# driver_board_ribbon.net
KiCad netlist of a schematic drawn in EAGLE
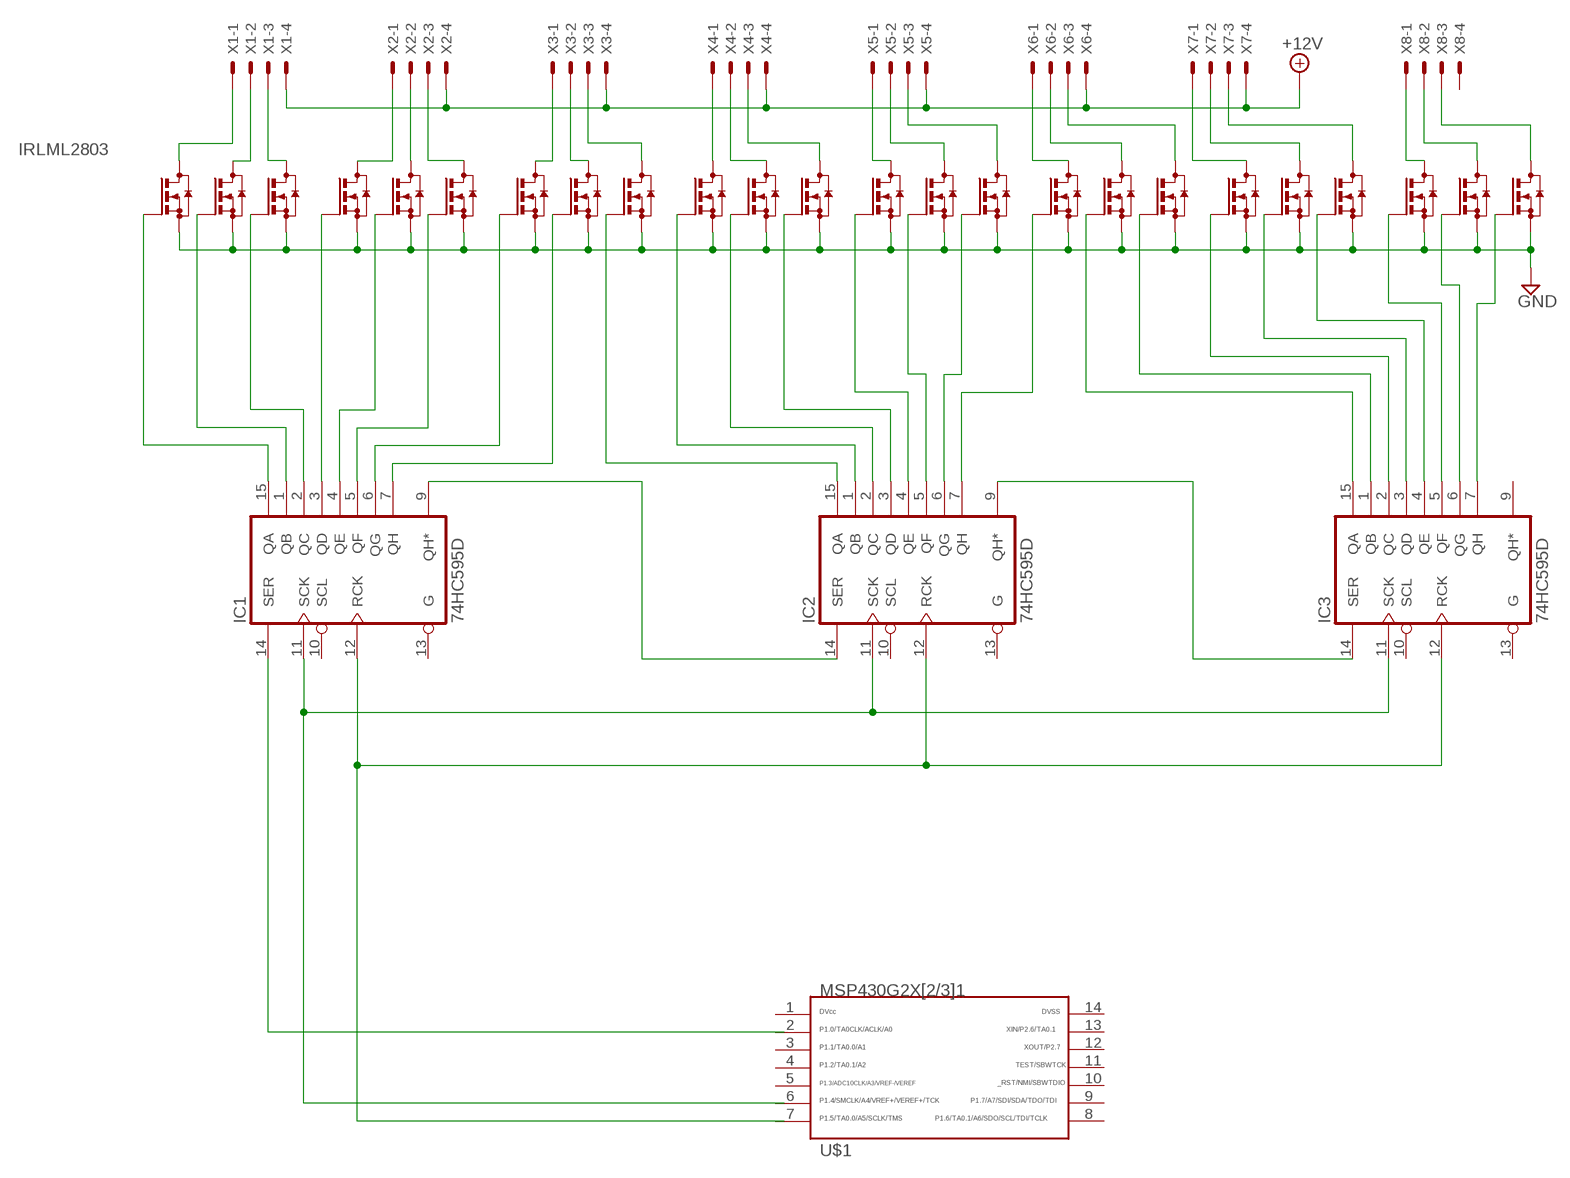
[diagram p0: schematic, sheet 1]

(export (version "E")
  (design (tool "Eeschema 10.0.6"))
  (components
    (comp (ref "IC1")
      (value "74HC595D")
      (footprint "eagle-import:SO16")
      (libsource (lib "eagle-import") (part "74595DHC"))
    )
    (comp (ref "IC2")
      (value "74HC595D")
      (footprint "eagle-import:SO16")
      (libsource (lib "eagle-import") (part "74595DHC"))
    )
    (comp (ref "IC3")
      (value "74HC595D")
      (footprint "eagle-import:SO16")
      (libsource (lib "eagle-import") (part "74595DHC"))
    )
    (comp (ref "U$1")
      (value "G2X[2/3]1---PW14")
      (footprint "eagle-import:PW14")
      (libsource (lib "eagle-import") (part "G2X[2/3]1---PW14"))
    )
    (comp (ref "U$3")
      (value "IRLML2803")
      (footprint "eagle-import:SOT23")
      (libsource (lib "eagle-import") (part "IRLML2803"))
    )
    (comp (ref "U$4")
      (value "IRLML2803")
      (footprint "eagle-import:SOT23")
      (libsource (lib "eagle-import") (part "IRLML2803"))
    )
    (comp (ref "U$5")
      (value "IRLML2803")
      (footprint "eagle-import:SOT23")
      (libsource (lib "eagle-import") (part "IRLML2803"))
    )
    (comp (ref "U$6")
      (value "IRLML2803")
      (footprint "eagle-import:SOT23")
      (libsource (lib "eagle-import") (part "IRLML2803"))
    )
    (comp (ref "U$7")
      (value "IRLML2803")
      (footprint "eagle-import:SOT23")
      (libsource (lib "eagle-import") (part "IRLML2803"))
    )
    (comp (ref "U$8")
      (value "IRLML2803")
      (footprint "eagle-import:SOT23")
      (libsource (lib "eagle-import") (part "IRLML2803"))
    )
    (comp (ref "U$9")
      (value "IRLML2803")
      (footprint "eagle-import:SOT23")
      (libsource (lib "eagle-import") (part "IRLML2803"))
    )
    (comp (ref "U$10")
      (value "IRLML2803")
      (footprint "eagle-import:SOT23")
      (libsource (lib "eagle-import") (part "IRLML2803"))
    )
    (comp (ref "U$11")
      (value "IRLML2803")
      (footprint "eagle-import:SOT23")
      (libsource (lib "eagle-import") (part "IRLML2803"))
    )
    (comp (ref "U$12")
      (value "IRLML2803")
      (footprint "eagle-import:SOT23")
      (libsource (lib "eagle-import") (part "IRLML2803"))
    )
    (comp (ref "U$13")
      (value "IRLML2803")
      (footprint "eagle-import:SOT23")
      (libsource (lib "eagle-import") (part "IRLML2803"))
    )
    (comp (ref "U$14")
      (value "IRLML2803")
      (footprint "eagle-import:SOT23")
      (libsource (lib "eagle-import") (part "IRLML2803"))
    )
    (comp (ref "U$15")
      (value "IRLML2803")
      (footprint "eagle-import:SOT23")
      (libsource (lib "eagle-import") (part "IRLML2803"))
    )
    (comp (ref "U$16")
      (value "IRLML2803")
      (footprint "eagle-import:SOT23")
      (libsource (lib "eagle-import") (part "IRLML2803"))
    )
    (comp (ref "U$17")
      (value "IRLML2803")
      (footprint "eagle-import:SOT23")
      (libsource (lib "eagle-import") (part "IRLML2803"))
    )
    (comp (ref "U$18")
      (value "IRLML2803")
      (footprint "eagle-import:SOT23")
      (libsource (lib "eagle-import") (part "IRLML2803"))
    )
    (comp (ref "U$19")
      (value "IRLML2803")
      (footprint "eagle-import:SOT23")
      (libsource (lib "eagle-import") (part "IRLML2803"))
    )
    (comp (ref "U$20")
      (value "IRLML2803")
      (footprint "eagle-import:SOT23")
      (libsource (lib "eagle-import") (part "IRLML2803"))
    )
    (comp (ref "U$21")
      (value "IRLML2803")
      (footprint "eagle-import:SOT23")
      (libsource (lib "eagle-import") (part "IRLML2803"))
    )
    (comp (ref "U$22")
      (value "IRLML2803")
      (footprint "eagle-import:SOT23")
      (libsource (lib "eagle-import") (part "IRLML2803"))
    )
    (comp (ref "U$23")
      (value "IRLML2803")
      (footprint "eagle-import:SOT23")
      (libsource (lib "eagle-import") (part "IRLML2803"))
    )
    (comp (ref "U$24")
      (value "IRLML2803")
      (footprint "eagle-import:SOT23")
      (libsource (lib "eagle-import") (part "IRLML2803"))
    )
    (comp (ref "U$25")
      (value "IRLML2803")
      (footprint "eagle-import:SOT23")
      (libsource (lib "eagle-import") (part "IRLML2803"))
    )
    (comp (ref "U$26")
      (value "IRLML2803")
      (footprint "eagle-import:SOT23")
      (libsource (lib "eagle-import") (part "IRLML2803"))
    )
    (comp (ref "X1")
      (value "KK-156-4")
      (footprint "eagle-import:KK-156-4")
      (libsource (lib "eagle-import") (part "KK-156-4"))
    )
    (comp (ref "X2")
      (value "KK-156-4")
      (footprint "eagle-import:KK-156-4")
      (libsource (lib "eagle-import") (part "KK-156-4"))
    )
    (comp (ref "X3")
      (value "KK-156-4")
      (footprint "eagle-import:KK-156-4")
      (libsource (lib "eagle-import") (part "KK-156-4"))
    )
    (comp (ref "X4")
      (value "KK-156-4")
      (footprint "eagle-import:KK-156-4")
      (libsource (lib "eagle-import") (part "KK-156-4"))
    )
    (comp (ref "X5")
      (value "KK-156-4")
      (footprint "eagle-import:KK-156-4")
      (libsource (lib "eagle-import") (part "KK-156-4"))
    )
    (comp (ref "X6")
      (value "KK-156-4")
      (footprint "eagle-import:KK-156-4")
      (libsource (lib "eagle-import") (part "KK-156-4"))
    )
    (comp (ref "X7")
      (value "KK-156-4")
      (footprint "eagle-import:KK-156-4")
      (libsource (lib "eagle-import") (part "KK-156-4"))
    )
    (comp (ref "X8")
      (value "KK-156-4")
      (footprint "eagle-import:KK-156-4")
      (libsource (lib "eagle-import") (part "KK-156-4"))
    )
  )
  (nets
    (net (code "1") (name "+12V") (class "Default")
      (node (ref "X1") (pin "4") (pinfunction "S_4") (pintype "passive"))
      (node (ref "X2") (pin "4") (pinfunction "S_4") (pintype "passive"))
      (node (ref "X3") (pin "4") (pinfunction "S_4") (pintype "passive"))
      (node (ref "X4") (pin "4") (pinfunction "S_4") (pintype "passive"))
      (node (ref "X5") (pin "4") (pinfunction "S_4") (pintype "passive"))
      (node (ref "X6") (pin "4") (pinfunction "S_4") (pintype "passive"))
      (node (ref "X7") (pin "4") (pinfunction "S_4") (pintype "passive"))
    )
    (net (code "2") (name "GND") (class "Default")
      (node (ref "U$10") (pin "2") (pinfunction "S_2") (pintype "passive"))
      (node (ref "U$11") (pin "2") (pinfunction "S_2") (pintype "passive"))
      (node (ref "U$12") (pin "2") (pinfunction "S_2") (pintype "passive"))
      (node (ref "U$13") (pin "2") (pinfunction "S_2") (pintype "passive"))
      (node (ref "U$14") (pin "2") (pinfunction "S_2") (pintype "passive"))
      (node (ref "U$15") (pin "2") (pinfunction "S_2") (pintype "passive"))
      (node (ref "U$16") (pin "2") (pinfunction "S_2") (pintype "passive"))
      (node (ref "U$17") (pin "2") (pinfunction "S_2") (pintype "passive"))
      (node (ref "U$18") (pin "2") (pinfunction "S_2") (pintype "passive"))
      (node (ref "U$19") (pin "2") (pinfunction "S_2") (pintype "passive"))
      (node (ref "U$20") (pin "2") (pinfunction "S_2") (pintype "passive"))
      (node (ref "U$21") (pin "2") (pinfunction "S_2") (pintype "passive"))
      (node (ref "U$22") (pin "2") (pinfunction "S_2") (pintype "passive"))
      (node (ref "U$23") (pin "2") (pinfunction "S_2") (pintype "passive"))
      (node (ref "U$24") (pin "2") (pinfunction "S_2") (pintype "passive"))
      (node (ref "U$25") (pin "2") (pinfunction "S_2") (pintype "passive"))
      (node (ref "U$26") (pin "2") (pinfunction "S_2") (pintype "passive"))
      (node (ref "U$3") (pin "2") (pinfunction "S_2") (pintype "passive"))
      (node (ref "U$4") (pin "2") (pinfunction "S_2") (pintype "passive"))
      (node (ref "U$5") (pin "2") (pinfunction "S_2") (pintype "passive"))
      (node (ref "U$6") (pin "2") (pinfunction "S_2") (pintype "passive"))
      (node (ref "U$7") (pin "2") (pinfunction "S_2") (pintype "passive"))
      (node (ref "U$8") (pin "2") (pinfunction "S_2") (pintype "passive"))
      (node (ref "U$9") (pin "2") (pinfunction "S_2") (pintype "passive"))
    )
    (net (code "3") (name "Net-(IC1A-QA)") (class "Default")
      (node (ref "IC1") (pin "15") (pinfunction "QA_15") (pintype "tri_state"))
      (node (ref "U$3") (pin "1") (pinfunction "G_1") (pintype "passive"))
    )
    (net (code "4") (name "Net-(IC1A-QB)") (class "Default")
      (node (ref "IC1") (pin "1") (pinfunction "QB_1") (pintype "tri_state"))
      (node (ref "U$4") (pin "1") (pinfunction "G_1") (pintype "passive"))
    )
    (net (code "5") (name "Net-(IC1A-QC)") (class "Default")
      (node (ref "IC1") (pin "2") (pinfunction "QC_2") (pintype "tri_state"))
      (node (ref "U$5") (pin "1") (pinfunction "G_1") (pintype "passive"))
    )
    (net (code "6") (name "Net-(IC1A-QD)") (class "Default")
      (node (ref "IC1") (pin "3") (pinfunction "QD_3") (pintype "tri_state"))
      (node (ref "U$6") (pin "1") (pinfunction "G_1") (pintype "passive"))
    )
    (net (code "7") (name "Net-(IC1A-QE)") (class "Default")
      (node (ref "IC1") (pin "4") (pinfunction "QE_4") (pintype "tri_state"))
      (node (ref "U$7") (pin "1") (pinfunction "G_1") (pintype "passive"))
    )
    (net (code "8") (name "Net-(IC1A-QF)") (class "Default")
      (node (ref "IC1") (pin "5") (pinfunction "QF_5") (pintype "tri_state"))
      (node (ref "U$8") (pin "1") (pinfunction "G_1") (pintype "passive"))
    )
    (net (code "9") (name "Net-(IC1A-QG)") (class "Default")
      (node (ref "IC1") (pin "6") (pinfunction "QG_6") (pintype "tri_state"))
      (node (ref "U$9") (pin "1") (pinfunction "G_1") (pintype "passive"))
    )
    (net (code "10") (name "Net-(IC1A-QH)") (class "Default")
      (node (ref "IC1") (pin "7") (pinfunction "QH_7") (pintype "tri_state"))
      (node (ref "U$10") (pin "1") (pinfunction "G_1") (pintype "passive"))
    )
    (net (code "11") (name "Net-(IC1A-QH*)") (class "Default")
      (node (ref "IC1") (pin "9") (pinfunction "QH*_9") (pintype "tri_state"))
      (node (ref "IC2") (pin "14") (pinfunction "SER_14") (pintype "input"))
    )
    (net (code "12") (name "Net-(IC1A-RCK)") (class "Default")
      (node (ref "IC1") (pin "12") (pinfunction "RCK_12") (pintype "input"))
      (node (ref "IC2") (pin "12") (pinfunction "RCK_12") (pintype "input"))
      (node (ref "IC3") (pin "12") (pinfunction "RCK_12") (pintype "input"))
    )
    (net (code "13") (name "Net-(IC1A-SCK)") (class "Default")
      (node (ref "IC1") (pin "11") (pinfunction "SCK_11") (pintype "input"))
      (node (ref "IC2") (pin "11") (pinfunction "SCK_11") (pintype "input"))
      (node (ref "IC3") (pin "11") (pinfunction "SCK_11") (pintype "input"))
    )
    (net (code "14") (name "Net-(IC2A-QA)") (class "Default")
      (node (ref "IC2") (pin "15") (pinfunction "QA_15") (pintype "tri_state"))
      (node (ref "U$11") (pin "1") (pinfunction "G_1") (pintype "passive"))
    )
    (net (code "15") (name "Net-(IC2A-QB)") (class "Default")
      (node (ref "IC2") (pin "1") (pinfunction "QB_1") (pintype "tri_state"))
      (node (ref "U$12") (pin "1") (pinfunction "G_1") (pintype "passive"))
    )
    (net (code "16") (name "Net-(IC2A-QC)") (class "Default")
      (node (ref "IC2") (pin "2") (pinfunction "QC_2") (pintype "tri_state"))
      (node (ref "U$13") (pin "1") (pinfunction "G_1") (pintype "passive"))
    )
    (net (code "17") (name "Net-(IC2A-QD)") (class "Default")
      (node (ref "IC2") (pin "3") (pinfunction "QD_3") (pintype "tri_state"))
      (node (ref "U$14") (pin "1") (pinfunction "G_1") (pintype "passive"))
    )
    (net (code "18") (name "Net-(IC2A-QE)") (class "Default")
      (node (ref "IC2") (pin "4") (pinfunction "QE_4") (pintype "tri_state"))
      (node (ref "U$15") (pin "1") (pinfunction "G_1") (pintype "passive"))
    )
    (net (code "19") (name "Net-(IC2A-QF)") (class "Default")
      (node (ref "IC2") (pin "5") (pinfunction "QF_5") (pintype "tri_state"))
      (node (ref "U$16") (pin "1") (pinfunction "G_1") (pintype "passive"))
    )
    (net (code "20") (name "Net-(IC2A-QG)") (class "Default")
      (node (ref "IC2") (pin "6") (pinfunction "QG_6") (pintype "tri_state"))
      (node (ref "U$17") (pin "1") (pinfunction "G_1") (pintype "passive"))
    )
    (net (code "21") (name "Net-(IC2A-QH)") (class "Default")
      (node (ref "IC2") (pin "7") (pinfunction "QH_7") (pintype "tri_state"))
      (node (ref "U$18") (pin "1") (pinfunction "G_1") (pintype "passive"))
    )
    (net (code "22") (name "Net-(IC2A-QH*)") (class "Default")
      (node (ref "IC2") (pin "9") (pinfunction "QH*_9") (pintype "tri_state"))
      (node (ref "IC3") (pin "14") (pinfunction "SER_14") (pintype "input"))
    )
    (net (code "23") (name "Net-(IC3A-QA)") (class "Default")
      (node (ref "IC3") (pin "15") (pinfunction "QA_15") (pintype "tri_state"))
      (node (ref "U$19") (pin "1") (pinfunction "G_1") (pintype "passive"))
    )
    (net (code "24") (name "Net-(IC3A-QB)") (class "Default")
      (node (ref "IC3") (pin "1") (pinfunction "QB_1") (pintype "tri_state"))
      (node (ref "U$20") (pin "1") (pinfunction "G_1") (pintype "passive"))
    )
    (net (code "25") (name "Net-(IC3A-QC)") (class "Default")
      (node (ref "IC3") (pin "2") (pinfunction "QC_2") (pintype "tri_state"))
      (node (ref "U$21") (pin "1") (pinfunction "G_1") (pintype "passive"))
    )
    (net (code "26") (name "Net-(IC3A-QD)") (class "Default")
      (node (ref "IC3") (pin "3") (pinfunction "QD_3") (pintype "tri_state"))
      (node (ref "U$22") (pin "1") (pinfunction "G_1") (pintype "passive"))
    )
    (net (code "27") (name "Net-(IC3A-QE)") (class "Default")
      (node (ref "IC3") (pin "4") (pinfunction "QE_4") (pintype "tri_state"))
      (node (ref "U$23") (pin "1") (pinfunction "G_1") (pintype "passive"))
    )
    (net (code "28") (name "Net-(IC3A-QF)") (class "Default")
      (node (ref "IC3") (pin "5") (pinfunction "QF_5") (pintype "tri_state"))
      (node (ref "U$24") (pin "1") (pinfunction "G_1") (pintype "passive"))
    )
    (net (code "29") (name "Net-(IC3A-QG)") (class "Default")
      (node (ref "IC3") (pin "6") (pinfunction "QG_6") (pintype "tri_state"))
      (node (ref "U$25") (pin "1") (pinfunction "G_1") (pintype "passive"))
    )
    (net (code "30") (name "Net-(IC3A-QH)") (class "Default")
      (node (ref "IC3") (pin "7") (pinfunction "QH_7") (pintype "tri_state"))
      (node (ref "U$26") (pin "1") (pinfunction "G_1") (pintype "passive"))
    )
    (net (code "31") (name "Net-(U$3-D)") (class "Default")
      (node (ref "U$3") (pin "3") (pinfunction "D_3") (pintype "passive"))
      (node (ref "X1") (pin "1") (pinfunction "S_1") (pintype "passive"))
    )
    (net (code "32") (name "Net-(U$4-D)") (class "Default")
      (node (ref "U$4") (pin "3") (pinfunction "D_3") (pintype "passive"))
      (node (ref "X1") (pin "2") (pinfunction "S_2") (pintype "passive"))
    )
    (net (code "33") (name "Net-(U$5-D)") (class "Default")
      (node (ref "U$5") (pin "3") (pinfunction "D_3") (pintype "passive"))
      (node (ref "X1") (pin "3") (pinfunction "S_3") (pintype "passive"))
    )
    (net (code "34") (name "Net-(U$6-D)") (class "Default")
      (node (ref "U$6") (pin "3") (pinfunction "D_3") (pintype "passive"))
      (node (ref "X2") (pin "1") (pinfunction "S_1") (pintype "passive"))
    )
    (net (code "35") (name "Net-(U$7-D)") (class "Default")
      (node (ref "U$7") (pin "3") (pinfunction "D_3") (pintype "passive"))
      (node (ref "X2") (pin "2") (pinfunction "S_2") (pintype "passive"))
    )
    (net (code "36") (name "Net-(U$8-D)") (class "Default")
      (node (ref "U$8") (pin "3") (pinfunction "D_3") (pintype "passive"))
      (node (ref "X2") (pin "3") (pinfunction "S_3") (pintype "passive"))
    )
    (net (code "37") (name "Net-(U$9-D)") (class "Default")
      (node (ref "U$9") (pin "3") (pinfunction "D_3") (pintype "passive"))
      (node (ref "X3") (pin "1") (pinfunction "S_1") (pintype "passive"))
    )
    (net (code "38") (name "Net-(U$10-D)") (class "Default")
      (node (ref "U$10") (pin "3") (pinfunction "D_3") (pintype "passive"))
      (node (ref "X3") (pin "2") (pinfunction "S_2") (pintype "passive"))
    )
    (net (code "39") (name "Net-(U$11-D)") (class "Default")
      (node (ref "U$11") (pin "3") (pinfunction "D_3") (pintype "passive"))
      (node (ref "X3") (pin "3") (pinfunction "S_3") (pintype "passive"))
    )
    (net (code "40") (name "Net-(U$12-D)") (class "Default")
      (node (ref "U$12") (pin "3") (pinfunction "D_3") (pintype "passive"))
      (node (ref "X4") (pin "1") (pinfunction "S_1") (pintype "passive"))
    )
    (net (code "41") (name "Net-(U$13-D)") (class "Default")
      (node (ref "U$13") (pin "3") (pinfunction "D_3") (pintype "passive"))
      (node (ref "X4") (pin "2") (pinfunction "S_2") (pintype "passive"))
    )
    (net (code "42") (name "Net-(U$14-D)") (class "Default")
      (node (ref "U$14") (pin "3") (pinfunction "D_3") (pintype "passive"))
      (node (ref "X4") (pin "3") (pinfunction "S_3") (pintype "passive"))
    )
    (net (code "43") (name "Net-(U$15-D)") (class "Default")
      (node (ref "U$15") (pin "3") (pinfunction "D_3") (pintype "passive"))
      (node (ref "X5") (pin "1") (pinfunction "S_1") (pintype "passive"))
    )
    (net (code "44") (name "Net-(U$16-D)") (class "Default")
      (node (ref "U$16") (pin "3") (pinfunction "D_3") (pintype "passive"))
      (node (ref "X5") (pin "2") (pinfunction "S_2") (pintype "passive"))
    )
    (net (code "45") (name "Net-(U$17-D)") (class "Default")
      (node (ref "U$17") (pin "3") (pinfunction "D_3") (pintype "passive"))
      (node (ref "X5") (pin "3") (pinfunction "S_3") (pintype "passive"))
    )
    (net (code "46") (name "Net-(U$18-D)") (class "Default")
      (node (ref "U$18") (pin "3") (pinfunction "D_3") (pintype "passive"))
      (node (ref "X6") (pin "1") (pinfunction "S_1") (pintype "passive"))
    )
    (net (code "47") (name "Net-(U$19-D)") (class "Default")
      (node (ref "U$19") (pin "3") (pinfunction "D_3") (pintype "passive"))
      (node (ref "X6") (pin "2") (pinfunction "S_2") (pintype "passive"))
    )
    (net (code "48") (name "Net-(U$20-D)") (class "Default")
      (node (ref "U$20") (pin "3") (pinfunction "D_3") (pintype "passive"))
      (node (ref "X6") (pin "3") (pinfunction "S_3") (pintype "passive"))
    )
    (net (code "49") (name "Net-(U$21-D)") (class "Default")
      (node (ref "U$21") (pin "3") (pinfunction "D_3") (pintype "passive"))
      (node (ref "X7") (pin "1") (pinfunction "S_1") (pintype "passive"))
    )
    (net (code "50") (name "Net-(U$22-D)") (class "Default")
      (node (ref "U$22") (pin "3") (pinfunction "D_3") (pintype "passive"))
      (node (ref "X7") (pin "2") (pinfunction "S_2") (pintype "passive"))
    )
    (net (code "51") (name "Net-(U$23-D)") (class "Default")
      (node (ref "U$23") (pin "3") (pinfunction "D_3") (pintype "passive"))
      (node (ref "X7") (pin "3") (pinfunction "S_3") (pintype "passive"))
    )
    (net (code "52") (name "Net-(U$24-D)") (class "Default")
      (node (ref "U$24") (pin "3") (pinfunction "D_3") (pintype "passive"))
      (node (ref "X8") (pin "1") (pinfunction "S_1") (pintype "passive"))
    )
    (net (code "53") (name "Net-(U$25-D)") (class "Default")
      (node (ref "U$25") (pin "3") (pinfunction "D_3") (pintype "passive"))
      (node (ref "X8") (pin "2") (pinfunction "S_2") (pintype "passive"))
    )
    (net (code "54") (name "Net-(U$26-D)") (class "Default")
      (node (ref "U$26") (pin "3") (pinfunction "D_3") (pintype "passive"))
      (node (ref "X8") (pin "3") (pinfunction "S_3") (pintype "passive"))
    )
    (net (code "55") (name "unconnected-(IC1A-G-Pad13)") (class "Default")
      (node (ref "IC1") (pin "13") (pinfunction "G_13") (pintype "input"))
    )
    (net (code "56") (name "unconnected-(IC1A-SCL-Pad10)") (class "Default")
      (node (ref "IC1") (pin "10") (pinfunction "SCL_10") (pintype "input"))
    )
    (net (code "57") (name "unconnected-(IC1A-SER-Pad14)") (class "Default")
      (node (ref "IC1") (pin "14") (pinfunction "SER_14") (pintype "input"))
    )
    (net (code "58") (name "unconnected-(IC2A-G-Pad13)") (class "Default")
      (node (ref "IC2") (pin "13") (pinfunction "G_13") (pintype "input"))
    )
    (net (code "59") (name "unconnected-(IC2A-SCL-Pad10)") (class "Default")
      (node (ref "IC2") (pin "10") (pinfunction "SCL_10") (pintype "input"))
    )
    (net (code "60") (name "unconnected-(IC3A-G-Pad13)") (class "Default")
      (node (ref "IC3") (pin "13") (pinfunction "G_13") (pintype "input"))
    )
    (net (code "61") (name "unconnected-(IC3A-QH*-Pad9)") (class "Default")
      (node (ref "IC3") (pin "9") (pinfunction "QH*_9") (pintype "tri_state"))
    )
    (net (code "62") (name "unconnected-(IC3A-SCL-Pad10)") (class "Default")
      (node (ref "IC3") (pin "10") (pinfunction "SCL_10") (pintype "input"))
    )
    (net (code "63") (name "unconnected-(U$1-Pad1)") (class "Default")
      (node (ref "U$1") (pin "1") (pinfunction "1_1") (pintype "bidirectional"))
    )
    (net (code "64") (name "unconnected-(U$1-Pad2)") (class "Default")
      (node (ref "U$1") (pin "2") (pinfunction "2_2") (pintype "bidirectional"))
    )
    (net (code "65") (name "unconnected-(U$1-Pad3)") (class "Default")
      (node (ref "U$1") (pin "3") (pinfunction "3_3") (pintype "bidirectional"))
    )
    (net (code "66") (name "unconnected-(U$1-Pad4)") (class "Default")
      (node (ref "U$1") (pin "4") (pinfunction "4_4") (pintype "bidirectional"))
    )
    (net (code "67") (name "unconnected-(U$1-Pad5)") (class "Default")
      (node (ref "U$1") (pin "5") (pinfunction "5_5") (pintype "bidirectional"))
    )
    (net (code "68") (name "unconnected-(U$1-Pad6)") (class "Default")
      (node (ref "U$1") (pin "6") (pinfunction "6_6") (pintype "bidirectional"))
    )
    (net (code "69") (name "unconnected-(U$1-Pad7)") (class "Default")
      (node (ref "U$1") (pin "7") (pinfunction "7_7") (pintype "bidirectional"))
    )
    (net (code "70") (name "unconnected-(U$1-Pad8)") (class "Default")
      (node (ref "U$1") (pin "8") (pinfunction "8_8") (pintype "bidirectional"))
    )
    (net (code "71") (name "unconnected-(U$1-Pad9)") (class "Default")
      (node (ref "U$1") (pin "9") (pinfunction "9_9") (pintype "bidirectional"))
    )
    (net (code "72") (name "unconnected-(U$1-Pad10)") (class "Default")
      (node (ref "U$1") (pin "10") (pinfunction "10_10") (pintype "bidirectional"))
    )
    (net (code "73") (name "unconnected-(U$1-Pad11)") (class "Default")
      (node (ref "U$1") (pin "11") (pinfunction "11_11") (pintype "bidirectional"))
    )
    (net (code "74") (name "unconnected-(U$1-Pad12)") (class "Default")
      (node (ref "U$1") (pin "12") (pinfunction "12_12") (pintype "bidirectional"))
    )
    (net (code "75") (name "unconnected-(U$1-Pad13)") (class "Default")
      (node (ref "U$1") (pin "13") (pinfunction "13_13") (pintype "bidirectional"))
    )
    (net (code "76") (name "unconnected-(U$1-Pad14)") (class "Default")
      (node (ref "U$1") (pin "14") (pinfunction "14_14") (pintype "bidirectional"))
    )
    (net (code "77") (name "unconnected-(X8D-S-Pad4)") (class "Default")
      (node (ref "X8") (pin "4") (pinfunction "S_4") (pintype "passive"))
    )
  )
)
